# giraffe-cjd-simple.net
KiCad netlist of a schematic drawn in EAGLE
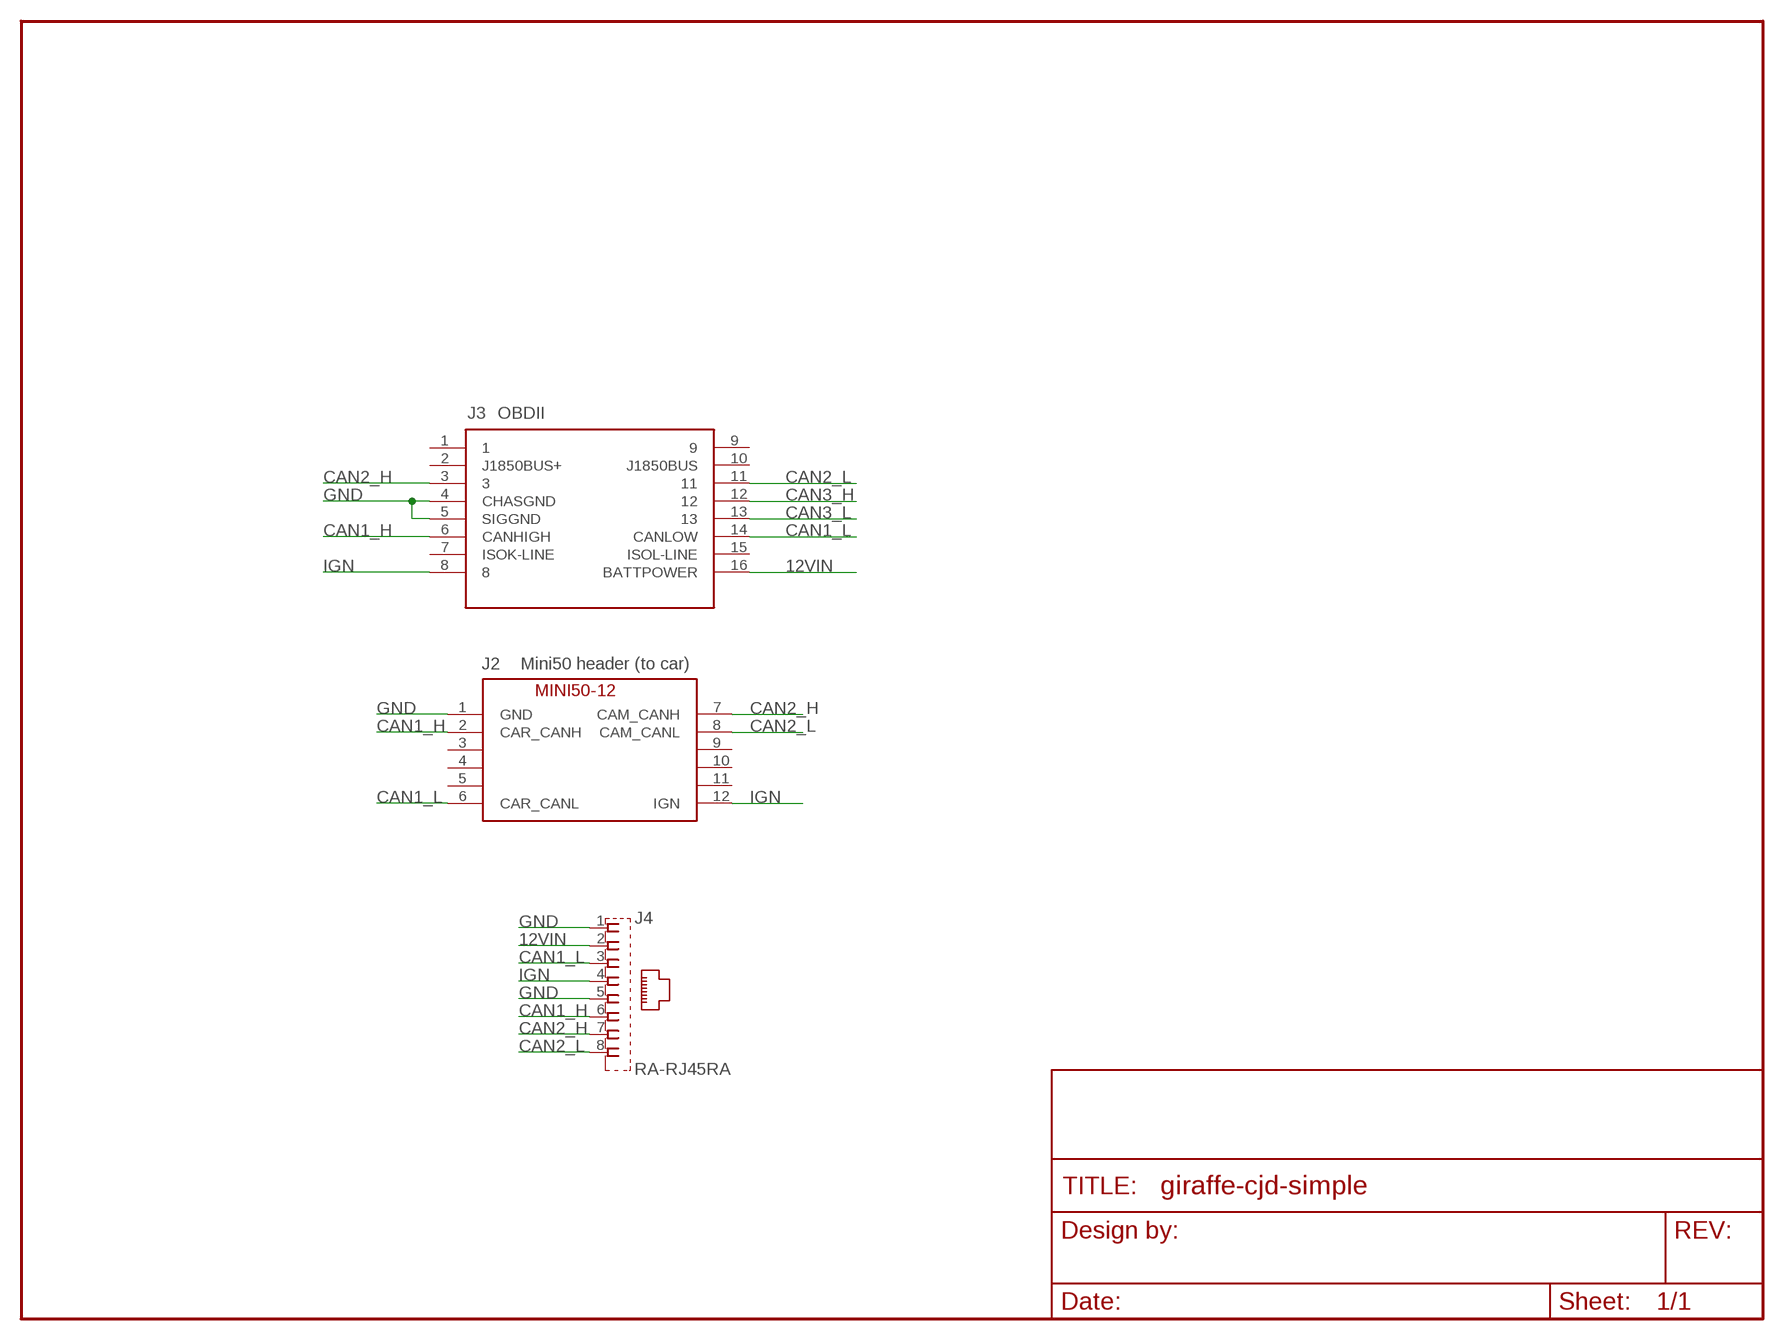
[diagram p0: schematic, sheet 1]

(export (version "E")
  (design (tool "Eeschema 10.0.6"))
  (components
    (comp (ref "FRAME1")
      (value "FRAME-LETTERNO_PACKAGE")
      (footprint "eagle-import:DUMMY")
      (fields (field (name "DESIGNER") "adhintz"))
      (libsource (lib "eagle-import") (part "FRAME-LETTERNO_PACKAGE"))
    )
    (comp (ref "J2")
      (value "MINI50MINI50-12-VERT")
      (footprint "eagle-import:MINI50-12")
      (libsource (lib "eagle-import") (part "MINI50MINI50-12-VERT"))
    )
    (comp (ref "J3")
      (value "OBDII-FEMALE-CUT")
      (footprint "eagle-import:OBDII-FEMALE-MIDCUT")
      (libsource (lib "eagle-import") (part "OBDII-FEMALE-CUT"))
    )
    (comp (ref "J4")
      (value "RA-RJ45RA")
      (footprint "eagle-import:RA-RJ45")
      (libsource (lib "eagle-import") (part "RA-RJ45RA"))
    )
  )
  (nets
    (net (code "1") (name "/12VIN") (class "Default")
      (node (ref "J3") (pin "16") (pinfunction "BATTPOWER_16") (pintype "bidirectional"))
      (node (ref "J4") (pin "2") (pinfunction "2_2") (pintype "passive"))
    )
    (net (code "2") (name "/CAN1_H") (class "Default")
      (node (ref "J2") (pin "2") (pinfunction "CAR_CANH_2") (pintype "bidirectional"))
      (node (ref "J3") (pin "6") (pinfunction "CANHIGH_6") (pintype "bidirectional"))
      (node (ref "J4") (pin "6") (pinfunction "6_6") (pintype "passive"))
    )
    (net (code "3") (name "/CAN1_L") (class "Default")
      (node (ref "J2") (pin "6") (pinfunction "CAR_CANL_6") (pintype "bidirectional"))
      (node (ref "J3") (pin "14") (pinfunction "CANLOW_14") (pintype "bidirectional"))
      (node (ref "J4") (pin "3") (pinfunction "3_3") (pintype "passive"))
    )
    (net (code "4") (name "/CAN2_H") (class "Default")
      (node (ref "J2") (pin "7") (pinfunction "CAM_CANH_7") (pintype "bidirectional"))
      (node (ref "J3") (pin "3") (pinfunction "3_3") (pintype "bidirectional"))
      (node (ref "J4") (pin "7") (pinfunction "7_7") (pintype "passive"))
    )
    (net (code "5") (name "/CAN2_L") (class "Default")
      (node (ref "J2") (pin "8") (pinfunction "CAM_CANL_8") (pintype "bidirectional"))
      (node (ref "J3") (pin "11") (pinfunction "11_11") (pintype "bidirectional"))
      (node (ref "J4") (pin "8") (pinfunction "8_8") (pintype "passive"))
    )
    (net (code "6") (name "/CAN3_H") (class "Default")
      (node (ref "J3") (pin "12") (pinfunction "12_12") (pintype "bidirectional"))
    )
    (net (code "7") (name "/CAN3_L") (class "Default")
      (node (ref "J3") (pin "13") (pinfunction "13_13") (pintype "bidirectional"))
    )
    (net (code "8") (name "/GND") (class "Default")
      (node (ref "J2") (pin "1") (pinfunction "GND_1") (pintype "power_in"))
      (node (ref "J3") (pin "4") (pinfunction "CHASGND_4") (pintype "bidirectional"))
      (node (ref "J3") (pin "5") (pinfunction "SIGGND_5") (pintype "bidirectional"))
      (node (ref "J4") (pin "1") (pinfunction "1_1") (pintype "passive"))
      (node (ref "J4") (pin "5") (pinfunction "5_5") (pintype "passive"))
    )
    (net (code "9") (name "/IGN") (class "Default")
      (node (ref "J2") (pin "12") (pinfunction "IGN_12") (pintype "power_in"))
      (node (ref "J3") (pin "8") (pinfunction "8_8") (pintype "bidirectional"))
      (node (ref "J4") (pin "4") (pinfunction "4_4") (pintype "passive"))
    )
    (net (code "10") (name "unconnected-(J2-Pad3)") (class "Default")
      (node (ref "J2") (pin "3") (pintype "bidirectional"))
    )
    (net (code "11") (name "unconnected-(J2-Pad4)") (class "Default")
      (node (ref "J2") (pin "4") (pintype "bidirectional"))
    )
    (net (code "12") (name "unconnected-(J2-Pad5)") (class "Default")
      (node (ref "J2") (pin "5") (pintype "bidirectional"))
    )
    (net (code "13") (name "unconnected-(J2-Pad9)") (class "Default")
      (node (ref "J2") (pin "9") (pintype "bidirectional"))
    )
    (net (code "14") (name "unconnected-(J2-Pad10)") (class "Default")
      (node (ref "J2") (pin "10") (pintype "bidirectional"))
    )
    (net (code "15") (name "unconnected-(J2-Pad11)") (class "Default")
      (node (ref "J2") (pin "11") (pintype "bidirectional"))
    )
    (net (code "16") (name "unconnected-(J3-ISOK-LINE-Pad7)") (class "Default")
      (node (ref "J3") (pin "7") (pinfunction "ISOK-LINE_7") (pintype "bidirectional"))
    )
    (net (code "17") (name "unconnected-(J3-ISOL-LINE-Pad15)") (class "Default")
      (node (ref "J3") (pin "15") (pinfunction "ISOL-LINE_15") (pintype "bidirectional"))
    )
    (net (code "18") (name "unconnected-(J3-J1850BUS+-Pad2)") (class "Default")
      (node (ref "J3") (pin "2") (pinfunction "J1850BUS+_2") (pintype "bidirectional"))
    )
    (net (code "19") (name "unconnected-(J3-J1850BUS-Pad10)") (class "Default")
      (node (ref "J3") (pin "10") (pinfunction "J1850BUS_10") (pintype "bidirectional"))
    )
    (net (code "20") (name "unconnected-(J3-Pad1)") (class "Default")
      (node (ref "J3") (pin "1") (pinfunction "1_1") (pintype "bidirectional"))
    )
    (net (code "21") (name "unconnected-(J3-Pad9)") (class "Default")
      (node (ref "J3") (pin "9") (pinfunction "9_9") (pintype "bidirectional"))
    )
  )
)
